# XmasTree.net
KiCad netlist of a schematic drawn in EAGLE
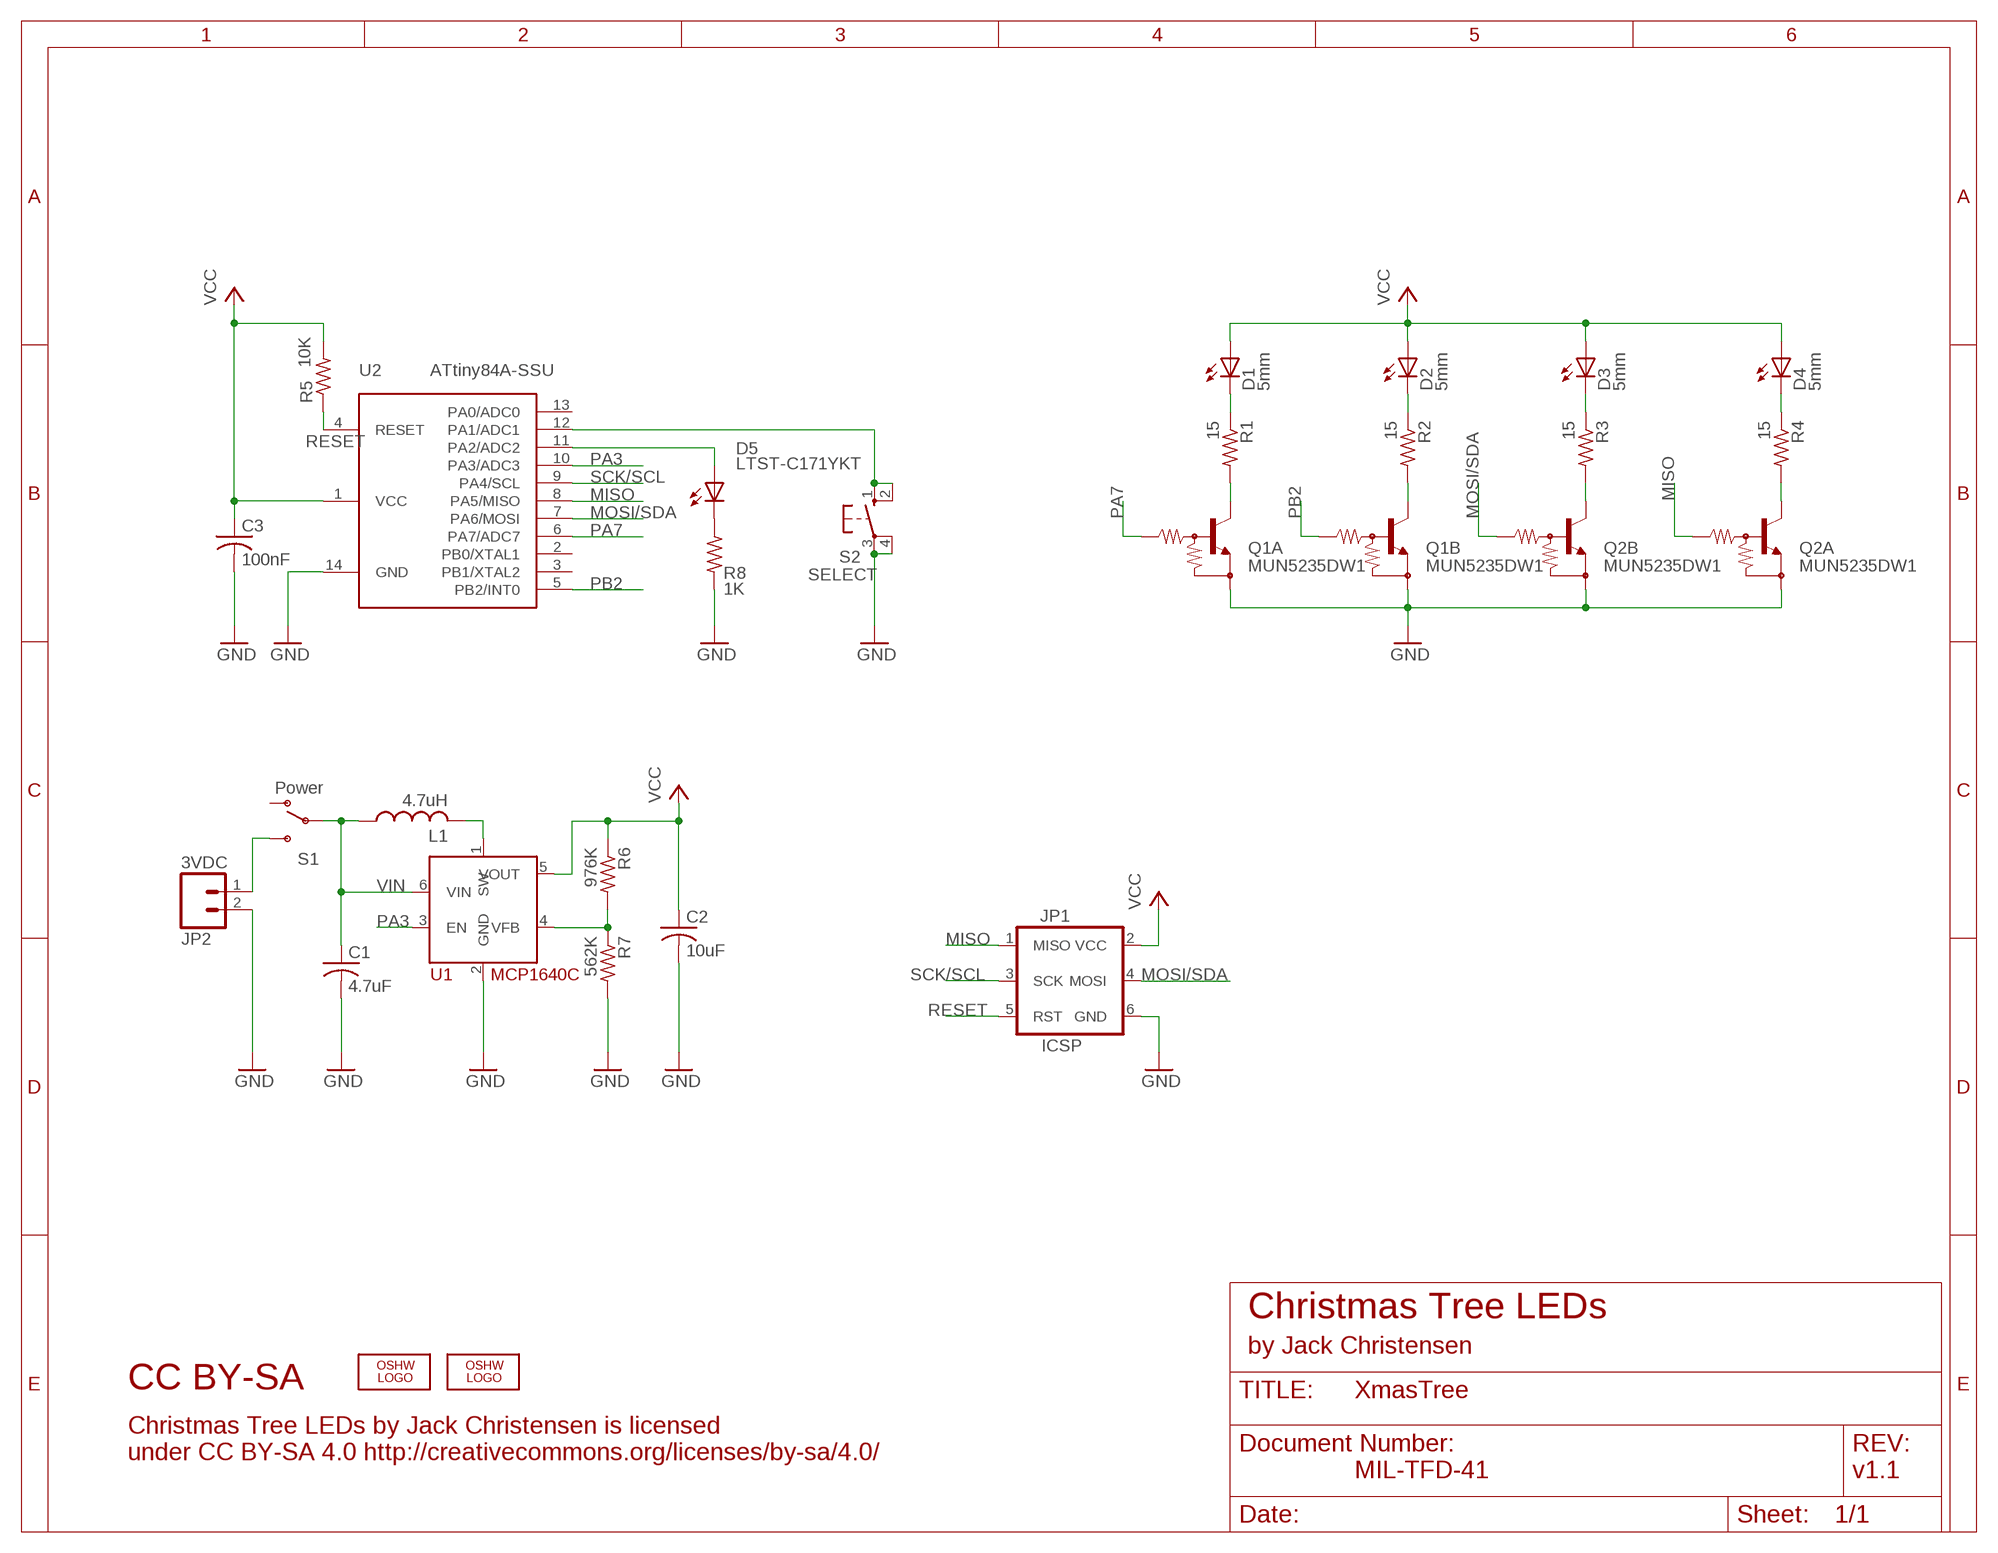
[diagram p0: schematic, sheet 1]

(export (version "E")
  (design (tool "Eeschema 10.0.6"))
  (components
    (comp (ref "C1")
      (value "4.7uF")
      (footprint "eagle-import:M0805")
      (libsource (lib "eagle-import") (part "C-USM0805"))
    )
    (comp (ref "C2")
      (value "10uF")
      (footprint "eagle-import:M0805")
      (libsource (lib "eagle-import") (part "C-USM0805"))
    )
    (comp (ref "C3")
      (value "100nF")
      (footprint "eagle-import:M0805")
      (libsource (lib "eagle-import") (part "C-USM0805"))
    )
    (comp (ref "D1")
      (value "5mm")
      (footprint "eagle-import:LED5MM")
      (libsource (lib "eagle-import") (part "LED5MM"))
    )
    (comp (ref "D2")
      (value "5mm")
      (footprint "eagle-import:LED5MM")
      (libsource (lib "eagle-import") (part "LED5MM"))
    )
    (comp (ref "D3")
      (value "5mm")
      (footprint "eagle-import:LED5MM")
      (libsource (lib "eagle-import") (part "LED5MM"))
    )
    (comp (ref "D4")
      (value "5mm")
      (footprint "eagle-import:LED5MM")
      (libsource (lib "eagle-import") (part "LED5MM"))
    )
    (comp (ref "D5")
      (value "LTST-C171YKT")
      (footprint "eagle-import:D0805")
      (libsource (lib "eagle-import") (part "LEDD0805"))
    )
    (comp (ref "JP1")
      (value "ICSP")
      (footprint "eagle-import:2X3_LOCK")
      (libsource (lib "eagle-import") (part "AVR_SPI_PRG_62X3_LOCK"))
    )
    (comp (ref "JP2")
      (value "3VDC")
      (footprint "eagle-import:1X02_LONGPADS")
      (libsource (lib "eagle-import") (part "M02"))
    )
    (comp (ref "L1")
      (value "4.7uH")
      (footprint "eagle-import:C1210K")
      (libsource (lib "eagle-import") (part "INDUCTORC1210K"))
    )
    (comp (ref "LOGO1")
      (value "OSHW_LOGO_8MILX0150-NT")
      (footprint "eagle-import:OSHW_8X150_NOTEXT")
      (libsource (lib "eagle-import") (part "OSHW_LOGO_8MILX0150-NT"))
    )
    (comp (ref "LOGO2")
      (value "OSHW_LOGO_8MILX0150-NT")
      (footprint "eagle-import:OSHW_8X150_NOTEXT")
      (libsource (lib "eagle-import") (part "OSHW_LOGO_8MILX0150-NT"))
    )
    (comp (ref "Q1")
      (value "MUN5235DW1")
      (footprint "eagle-import:SOT363_PHILIPS")
      (libsource (lib "eagle-import") (part "MUN52XXSOT363"))
    )
    (comp (ref "Q2")
      (value "MUN5235DW1")
      (footprint "eagle-import:SOT363_PHILIPS")
      (libsource (lib "eagle-import") (part "MUN52XXSOT363"))
    )
    (comp (ref "R1")
      (value "15")
      (footprint "eagle-import:M0805")
      (libsource (lib "eagle-import") (part "R-US_M0805"))
    )
    (comp (ref "R2")
      (value "15")
      (footprint "eagle-import:M0805")
      (libsource (lib "eagle-import") (part "R-US_M0805"))
    )
    (comp (ref "R3")
      (value "15")
      (footprint "eagle-import:M0805")
      (libsource (lib "eagle-import") (part "R-US_M0805"))
    )
    (comp (ref "R4")
      (value "15")
      (footprint "eagle-import:M0805")
      (libsource (lib "eagle-import") (part "R-US_M0805"))
    )
    (comp (ref "R5")
      (value "10K")
      (footprint "eagle-import:M0805")
      (libsource (lib "eagle-import") (part "R-US_M0805"))
    )
    (comp (ref "R6")
      (value "976K")
      (footprint "eagle-import:M0805")
      (libsource (lib "eagle-import") (part "R-US_M0805"))
    )
    (comp (ref "R7")
      (value "562K")
      (footprint "eagle-import:M0805")
      (libsource (lib "eagle-import") (part "R-US_M0805"))
    )
    (comp (ref "R8")
      (value "1K")
      (footprint "eagle-import:M0805")
      (libsource (lib "eagle-import") (part "R-US_M0805"))
    )
    (comp (ref "S1")
      (value "Power")
      (footprint "eagle-import:JS102011CQN")
      (libsource (lib "eagle-import") (part "SWITCH-SPST"))
    )
    (comp (ref "S2")
      (value "SELECT")
      (footprint "eagle-import:B3F-10XXOCT")
      (libsource (lib "eagle-import") (part "10-XXOCT"))
    )
    (comp (ref "U1")
      (value "MCP1640C")
      (footprint "eagle-import:SOT23-6")
      (libsource (lib "eagle-import") (part "MCP1640"))
    )
    (comp (ref "U2")
      (value "ATtiny84A-SSU")
      (footprint "eagle-import:SO14")
      (libsource (lib "eagle-import") (part "ATTINYX4SO14"))
    )
  )
  (nets
    (net (code "1") (name "/MISO") (class "Default")
      (node (ref "JP1") (pin "1") (pinfunction "MISO_1") (pintype "passive"))
      (node (ref "Q2") (pin "5") (pinfunction "B_5") (pintype "passive"))
      (node (ref "U2") (pin "8") (pinfunction "PA5/MISO_8") (pintype "bidirectional"))
    )
    (net (code "2") (name "/MOSI{slash}SDA") (class "Default")
      (node (ref "JP1") (pin "4") (pinfunction "MOSI_4") (pintype "passive"))
      (node (ref "Q2") (pin "2") (pinfunction "B_2") (pintype "passive"))
      (node (ref "U2") (pin "7") (pinfunction "PA6/MOSI_7") (pintype "bidirectional"))
    )
    (net (code "3") (name "/PA3") (class "Default")
      (node (ref "U1") (pin "3") (pinfunction "EN_3") (pintype "passive"))
      (node (ref "U2") (pin "10") (pinfunction "PA3/ADC3_10") (pintype "bidirectional"))
    )
    (net (code "4") (name "/PA7") (class "Default")
      (node (ref "Q1") (pin "5") (pinfunction "B_5") (pintype "passive"))
      (node (ref "U2") (pin "6") (pinfunction "PA7/ADC7_6") (pintype "bidirectional"))
    )
    (net (code "5") (name "/PB2") (class "Default")
      (node (ref "Q1") (pin "2") (pinfunction "B_2") (pintype "passive"))
      (node (ref "U2") (pin "5") (pinfunction "PB2/INT0_5") (pintype "bidirectional"))
    )
    (net (code "6") (name "/RESET") (class "Default")
      (node (ref "JP1") (pin "5") (pinfunction "RST_5") (pintype "passive"))
      (node (ref "R5") (pin "1") (pinfunction "1_1") (pintype "passive"))
      (node (ref "U2") (pin "4") (pinfunction "RESET_4") (pintype "bidirectional"))
    )
    (net (code "7") (name "/SCK{slash}SCL") (class "Default")
      (node (ref "JP1") (pin "3") (pinfunction "SCK_3") (pintype "passive"))
      (node (ref "U2") (pin "9") (pinfunction "PA4/SCL_9") (pintype "bidirectional"))
    )
    (net (code "8") (name "/VIN") (class "Default")
      (node (ref "C1") (pin "1") (pinfunction "1_1") (pintype "passive"))
      (node (ref "L1") (pin "1") (pinfunction "1_1") (pintype "passive"))
      (node (ref "S1") (pin "P$2") (pinfunction "P_P$2") (pintype "passive"))
      (node (ref "U1") (pin "6") (pinfunction "VIN_6") (pintype "passive"))
    )
    (net (code "9") (name "GND") (class "Default")
      (node (ref "C1") (pin "2") (pinfunction "2_2") (pintype "passive"))
      (node (ref "C2") (pin "2") (pinfunction "2_2") (pintype "passive"))
      (node (ref "C3") (pin "2") (pinfunction "2_2") (pintype "passive"))
      (node (ref "JP1") (pin "6") (pinfunction "GND_6") (pintype "passive"))
      (node (ref "JP2") (pin "2") (pinfunction "2_2") (pintype "passive"))
      (node (ref "Q1") (pin "1") (pinfunction "E_1") (pintype "passive"))
      (node (ref "Q1") (pin "4") (pinfunction "E_4") (pintype "passive"))
      (node (ref "Q2") (pin "1") (pinfunction "E_1") (pintype "passive"))
      (node (ref "Q2") (pin "4") (pinfunction "E_4") (pintype "passive"))
      (node (ref "R7") (pin "2") (pinfunction "2_2") (pintype "passive"))
      (node (ref "R8") (pin "2") (pinfunction "2_2") (pintype "passive"))
      (node (ref "S2") (pin "3") (pinfunction "P_3") (pintype "passive"))
      (node (ref "S2") (pin "4") (pinfunction "P1_4") (pintype "passive"))
      (node (ref "U1") (pin "2") (pinfunction "GND_2") (pintype "passive"))
      (node (ref "U2") (pin "14") (pinfunction "GND_14") (pintype "bidirectional"))
    )
    (net (code "10") (name "Net-(D1-C)") (class "Default")
      (node (ref "D1") (pin "K") (pinfunction "C_K") (pintype "passive"))
      (node (ref "R1") (pin "1") (pinfunction "1_1") (pintype "passive"))
    )
    (net (code "11") (name "Net-(D2-C)") (class "Default")
      (node (ref "D2") (pin "K") (pinfunction "C_K") (pintype "passive"))
      (node (ref "R2") (pin "1") (pinfunction "1_1") (pintype "passive"))
    )
    (net (code "12") (name "Net-(D3-C)") (class "Default")
      (node (ref "D3") (pin "K") (pinfunction "C_K") (pintype "passive"))
      (node (ref "R3") (pin "1") (pinfunction "1_1") (pintype "passive"))
    )
    (net (code "13") (name "Net-(D4-C)") (class "Default")
      (node (ref "D4") (pin "K") (pinfunction "C_K") (pintype "passive"))
      (node (ref "R4") (pin "1") (pinfunction "1_1") (pintype "passive"))
    )
    (net (code "14") (name "Net-(D5-C)") (class "Default")
      (node (ref "D5") (pin "K") (pinfunction "C_K") (pintype "passive"))
      (node (ref "R8") (pin "1") (pinfunction "1_1") (pintype "passive"))
    )
    (net (code "15") (name "Net-(Q1A-C)") (class "Default")
      (node (ref "Q1") (pin "3") (pinfunction "C_3") (pintype "passive"))
      (node (ref "R1") (pin "2") (pinfunction "2_2") (pintype "passive"))
    )
    (net (code "16") (name "Net-(Q1B-C)") (class "Default")
      (node (ref "Q1") (pin "6") (pinfunction "C_6") (pintype "passive"))
      (node (ref "R2") (pin "2") (pinfunction "2_2") (pintype "passive"))
    )
    (net (code "17") (name "Net-(Q2A-C)") (class "Default")
      (node (ref "Q2") (pin "3") (pinfunction "C_3") (pintype "passive"))
      (node (ref "R4") (pin "2") (pinfunction "2_2") (pintype "passive"))
    )
    (net (code "18") (name "Net-(Q2B-C)") (class "Default")
      (node (ref "Q2") (pin "6") (pinfunction "C_6") (pintype "passive"))
      (node (ref "R3") (pin "2") (pinfunction "2_2") (pintype "passive"))
    )
    (net (code "19") (name "Net-(S1-S)") (class "Default")
      (node (ref "JP2") (pin "1") (pinfunction "1_1") (pintype "passive"))
      (node (ref "S1") (pin "P$3") (pinfunction "S_P$3") (pintype "passive"))
    )
    (net (code "20") (name "Net-(S2-S)") (class "Default")
      (node (ref "S2") (pin "1") (pinfunction "S_1") (pintype "passive"))
      (node (ref "S2") (pin "2") (pinfunction "S1_2") (pintype "passive"))
      (node (ref "U2") (pin "12") (pinfunction "PA1/ADC1_12") (pintype "bidirectional"))
    )
    (net (code "21") (name "Net-(U1-SW)") (class "Default")
      (node (ref "L1") (pin "2") (pinfunction "2_2") (pintype "passive"))
      (node (ref "U1") (pin "1") (pinfunction "SW_1") (pintype "passive"))
    )
    (net (code "22") (name "Net-(U1-VFB)") (class "Default")
      (node (ref "R6") (pin "2") (pinfunction "2_2") (pintype "passive"))
      (node (ref "R7") (pin "1") (pinfunction "1_1") (pintype "passive"))
      (node (ref "U1") (pin "4") (pinfunction "VFB_4") (pintype "passive"))
    )
    (net (code "23") (name "Net-(U2-PA2{slash}ADC2)") (class "Default")
      (node (ref "D5") (pin "A") (pinfunction "A_A") (pintype "passive"))
      (node (ref "U2") (pin "11") (pinfunction "PA2/ADC2_11") (pintype "bidirectional"))
    )
    (net (code "24") (name "VCC") (class "Default")
      (node (ref "C2") (pin "1") (pinfunction "1_1") (pintype "passive"))
      (node (ref "C3") (pin "1") (pinfunction "1_1") (pintype "passive"))
      (node (ref "D1") (pin "A") (pinfunction "A_A") (pintype "passive"))
      (node (ref "D2") (pin "A") (pinfunction "A_A") (pintype "passive"))
      (node (ref "D3") (pin "A") (pinfunction "A_A") (pintype "passive"))
      (node (ref "D4") (pin "A") (pinfunction "A_A") (pintype "passive"))
      (node (ref "JP1") (pin "2") (pinfunction "VCC_2") (pintype "passive"))
      (node (ref "R5") (pin "2") (pinfunction "2_2") (pintype "passive"))
      (node (ref "R6") (pin "1") (pinfunction "1_1") (pintype "passive"))
      (node (ref "U1") (pin "5") (pinfunction "VOUT_5") (pintype "passive"))
      (node (ref "U2") (pin "1") (pinfunction "VCC_1") (pintype "bidirectional"))
    )
    (net (code "25") (name "unconnected-(S1-O-PadP$1)") (class "Default")
      (node (ref "S1") (pin "P$1") (pinfunction "O_P$1") (pintype "passive"))
    )
    (net (code "26") (name "unconnected-(U2-PA0{slash}ADC0-Pad13)") (class "Default")
      (node (ref "U2") (pin "13") (pinfunction "PA0/ADC0_13") (pintype "bidirectional"))
    )
    (net (code "27") (name "unconnected-(U2-PB0{slash}XTAL1-Pad2)") (class "Default")
      (node (ref "U2") (pin "2") (pinfunction "PB0/XTAL1_2") (pintype "bidirectional"))
    )
    (net (code "28") (name "unconnected-(U2-PB1{slash}XTAL2-Pad3)") (class "Default")
      (node (ref "U2") (pin "3") (pinfunction "PB1/XTAL2_3") (pintype "bidirectional"))
    )
  )
)
